# Diagnostics.net
KiCad netlist of a schematic drawn in Altium Designer
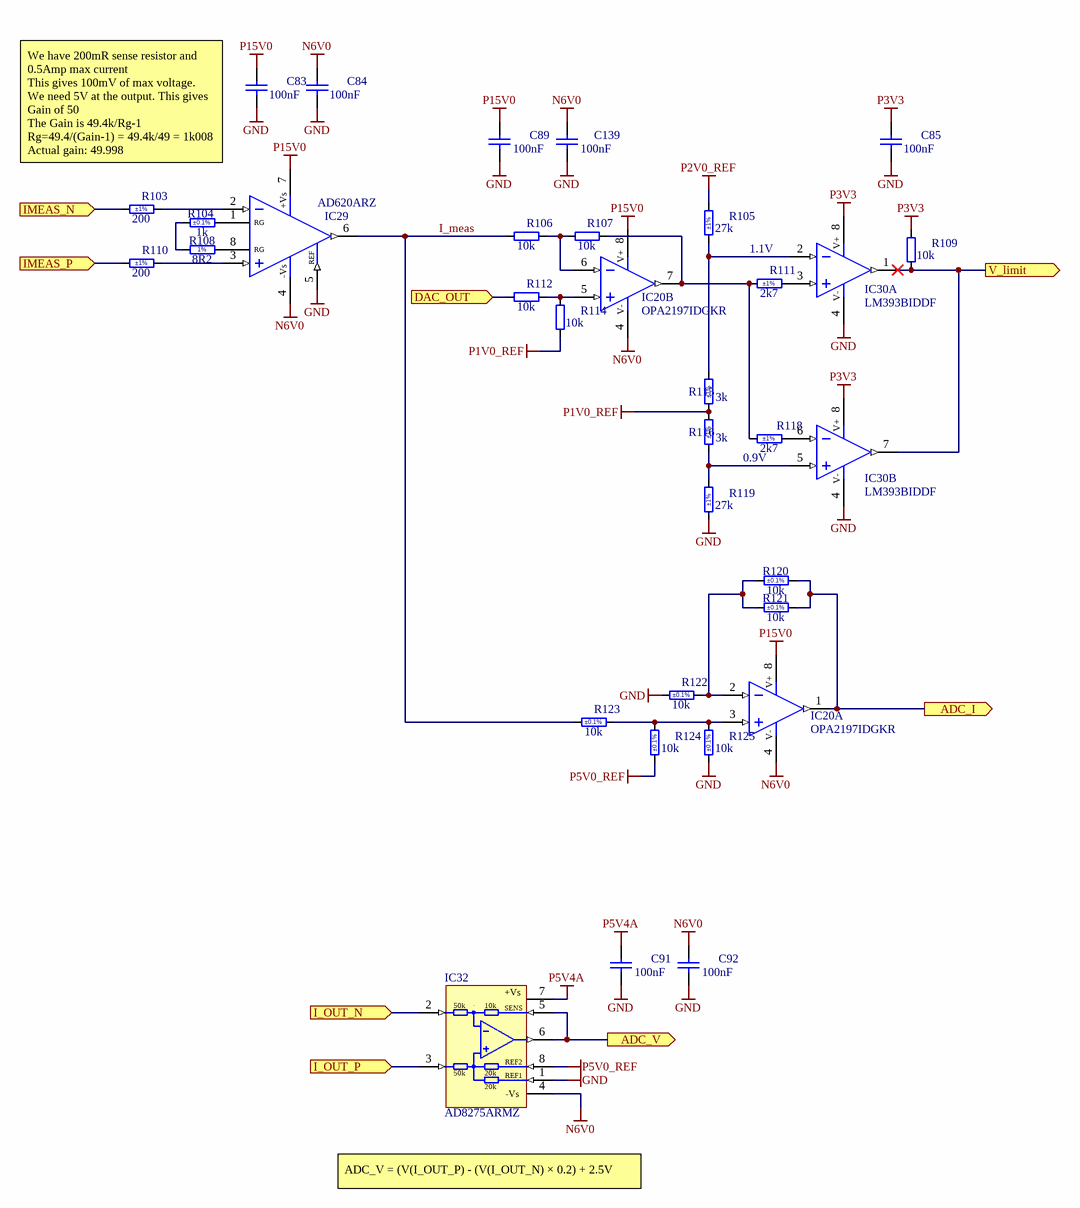
[diagram p0: Diagnostics.SchDoc]

(export (version "E")
  (design (tool "Eeschema 10.0.6"))
  (components
    (comp (ref "C83")
      (value "100nF")
      (footprint "CAPC1005X55N")
      (description "Non-polarised capacitor")
      (fields
        (field (name "PART NUMBER") "CC0402_100NF_16V_10%_X5R")
        (field (name "VOLTAGE") "16V")
        (field (name "AUTHOR") "CERN DEM JLC")
      )
      (libsource (lib "Capacitors") (part "Capacitor - non polarized"))
    )
    (comp (ref "C84")
      (value "100nF")
      (footprint "CAPC1005X55N")
      (description "Non-polarised capacitor")
      (fields
        (field (name "PART NUMBER") "CC0402_100NF_16V_10%_X5R")
        (field (name "VOLTAGE") "16V")
        (field (name "AUTHOR") "CERN DEM JLC")
      )
      (libsource (lib "Capacitors") (part "Capacitor - non polarized"))
    )
    (comp (ref "C85")
      (value "100nF")
      (footprint "CAPC1005X55N")
      (description "Non-polarised capacitor")
      (fields
        (field (name "PART NUMBER") "CC0402_100NF_16V_10%_X5R")
        (field (name "VOLTAGE") "16V")
        (field (name "AUTHOR") "CERN DEM JLC")
      )
      (libsource (lib "Capacitors") (part "Capacitor - non polarized"))
    )
    (comp (ref "C89")
      (value "100nF")
      (footprint "CAPC1005X55N")
      (description "Non-polarised capacitor")
      (fields
        (field (name "PART NUMBER") "CC0402_100NF_16V_10%_X5R")
        (field (name "VOLTAGE") "16V")
        (field (name "AUTHOR") "CERN DEM JLC")
      )
      (libsource (lib "Capacitors") (part "Capacitor - non polarized"))
    )
    (comp (ref "C91")
      (value "100nF")
      (footprint "CAPC1005X55N")
      (description "Non-polarised capacitor")
      (fields
        (field (name "PART NUMBER") "CC0402_100NF_16V_10%_X5R")
        (field (name "VOLTAGE") "16V")
        (field (name "AUTHOR") "CERN DEM JLC")
      )
      (libsource (lib "Capacitors") (part "Capacitor - non polarized"))
    )
    (comp (ref "C92")
      (value "100nF")
      (footprint "CAPC1005X55N")
      (description "Non-polarised capacitor")
      (fields
        (field (name "PART NUMBER") "CC0402_100NF_16V_10%_X5R")
        (field (name "VOLTAGE") "16V")
        (field (name "AUTHOR") "CERN DEM JLC")
      )
      (libsource (lib "Capacitors") (part "Capacitor - non polarized"))
    )
    (comp (ref "C139")
      (value "100nF")
      (footprint "CAPC1005X55N")
      (description "Non-polarised capacitor")
      (fields
        (field (name "PART NUMBER") "CC0402_100NF_16V_10%_X5R")
        (field (name "VOLTAGE") "16V")
        (field (name "AUTHOR") "CERN DEM JLC")
      )
      (libsource (lib "Capacitors") (part "Capacitor - non polarized"))
    )
    (comp (ref "IC20")
      (value "OPA2197IDGKR")
      (footprint "SOP65P490X110-8N")
      (description "36-V, Precision, Rail-to-Rail Input Output, Low Offset Voltage Op Amp 8-VSSOP")
      (fields (field (name "AUTHOR") "GK"))
      (libsource (lib "ICs_Analog_Interfaces") (part "OA_OPA2197IDGKR"))
    )
    (comp (ref "IC29")
      (value "AD620ARZ")
      (footprint "SOIC127P600X175-8N")
      (description "Low Cost Low Power Instrumentation Amplifier")
      (fields
        (field (name "MANUFACTURER1 PART NUMBER") "AD620ARZ-REEL7")
        (field (name "AUTHOR") "CERN DEM JLC")
      )
      (libsource (lib "ICs And Semiconductors") (part "AD620"))
    )
    (comp (ref "IC30")
      (value "LM393BIDDF")
      (footprint "SOT65P280X110-8N")
      (description "Dual Operational Amplifier")
      (fields (field (name "MANUFACTURER") "TEXAS INSTRUMENTS") (field (name "AUTHOR") "CERN DEM HF"))
      (libsource (lib "ICs And Semiconductors") (part "Operational Amplifier x2 Type1"))
    )
    (comp (ref "IC32")
      (value "AD8275ARMZ")
      (footprint "SOP65P490X110-8N")
      (description "G = 0.2, Level Translation, 16-Bit ADC Driver")
      (fields
        (field (name "MANUFACTURER") "ANALOG DEVICES")
        (field (name "MANUFACTURER PART NUMBER") "AD8275ARM")
        (field (name "AUTHOR") "CERN DEM JLC")
      )
      (libsource (lib "ICs And Semiconductors") (part "AD8275"))
    )
    (comp (ref "R103")
      (value "200")
      (footprint "RESC1608X55N")
      (description "Resistor - 1%")
      (fields
        (field (name "TOLERANCE") "±1%")
        (field (name "PART NUMBER") "R0603_200R_1%_0.1W_100PPM")
        (field (name "POWER") "0.1W")
        (field (name "AUTHOR") "CERN DEM JLC")
      )
      (libsource (lib "Resistors") (part "Resistor - 1%"))
    )
    (comp (ref "R104")
      (value "1k")
      (footprint "RESC1005X40N")
      (description "Resistor - 0.1%")
      (fields
        (field (name "TOLERANCE") "±0.1%")
        (field (name "PART NUMBER") "R0402_1K_0.1%_0.063W_25PPM")
        (field (name "POWER") "0.063W")
        (field (name "AUTHOR") "CERN DEM BC")
      )
      (libsource (lib "Resistors") (part "Resistor - 0.1%"))
    )
    (comp (ref "R105")
      (value "27k")
      (footprint "RESC1005X40N")
      (description "Resistor - 1%")
      (fields
        (field (name "TOLERANCE") "±1%")
        (field (name "PART NUMBER") "R0402_27K_1%_0.0625W_100PPM")
        (field (name "POWER") "0.0625W")
        (field (name "AUTHOR") "CERN DEM JLC")
      )
      (libsource (lib "Resistors") (part "Resistor - 1%"))
    )
    (comp (ref "R106")
      (value "10k")
      (footprint "RESC1005X35N")
      (description "Resistor - 0.1%")
      (fields
        (field (name "PART NUMBER") "R0402_10K_0.1%_0.063W_25PPM")
        (field (name "POWER") "0.063W")
        (field (name "AUTHOR") "CERN DEM JMW")
      )
      (libsource (lib "Resistors") (part "Resistor - 0.1%"))
    )
    (comp (ref "R107")
      (value "10k")
      (footprint "RESC1005X35N")
      (description "Resistor - 0.1%")
      (fields
        (field (name "PART NUMBER") "R0402_10K_0.1%_0.063W_25PPM")
        (field (name "POWER") "0.063W")
        (field (name "AUTHOR") "CERN DEM JMW")
      )
      (libsource (lib "Resistors") (part "Resistor - 0.1%"))
    )
    (comp (ref "R108")
      (value "8R2")
      (footprint "RESC1608X55N")
      (description "Resistor - 1%")
      (fields
        (field (name "PART NUMBER") "R0603_8R2_1%_0.1W_200PPM")
        (field (name "POWER") "0.1W")
        (field (name "AUTHOR") "CERN DEM JLC")
      )
      (libsource (lib "") (part "Resistor - 1%_1"))
    )
    (comp (ref "R109")
      (value "10k")
      (footprint "RESC1005X35N")
      (description "Resistor - 0.1%")
      (fields
        (field (name "PART NUMBER") "R0402_10K_0.1%_0.063W_25PPM")
        (field (name "POWER") "0.063W")
        (field (name "AUTHOR") "CERN DEM JMW")
      )
      (libsource (lib "Resistors") (part "Resistor - 0.1%"))
    )
    (comp (ref "R110")
      (value "200")
      (footprint "RESC1608X55N")
      (description "Resistor - 1%")
      (fields
        (field (name "TOLERANCE") "±1%")
        (field (name "PART NUMBER") "R0603_200R_1%_0.1W_100PPM")
        (field (name "POWER") "0.1W")
        (field (name "AUTHOR") "CERN DEM JLC")
      )
      (libsource (lib "Resistors") (part "Resistor - 1%"))
    )
    (comp (ref "R111")
      (value "2k7")
      (footprint "RESC1005X40N")
      (description "Resistor - 1%")
      (fields
        (field (name "TOLERANCE") "±1%")
        (field (name "PART NUMBER") "R0402_2K7_1%_0.0625W_100PPM")
        (field (name "POWER") "0.0625W")
        (field (name "AUTHOR") "CERN DEM HF")
      )
      (libsource (lib "Resistors") (part "Resistor - 1%"))
    )
    (comp (ref "R112")
      (value "10k")
      (footprint "RESC1005X35N")
      (description "Resistor - 0.1%")
      (fields
        (field (name "PART NUMBER") "R0402_10K_0.1%_0.063W_25PPM")
        (field (name "POWER") "0.063W")
        (field (name "AUTHOR") "CERN DEM JMW")
      )
      (libsource (lib "Resistors") (part "Resistor - 0.1%"))
    )
    (comp (ref "R114")
      (value "10k")
      (footprint "RESC1005X35N")
      (description "Resistor - 0.1%")
      (fields
        (field (name "PART NUMBER") "R0402_10K_0.1%_0.063W_25PPM")
        (field (name "POWER") "0.063W")
        (field (name "AUTHOR") "CERN DEM JMW")
      )
      (libsource (lib "Resistors") (part "Resistor - 0.1%"))
    )
    (comp (ref "R115")
      (value "3k")
      (footprint "RESC1005X40N")
      (description "Resistor - 1%")
      (fields
        (field (name "TOLERANCE") "±1%")
        (field (name "PART NUMBER") "R0402_3K_1%_0.0625W_100PPM")
        (field (name "POWER") "0.0625W")
        (field (name "AUTHOR") "CERN DEM JLC")
      )
      (libsource (lib "Resistors") (part "Resistor - 1%"))
    )
    (comp (ref "R116")
      (value "3k")
      (footprint "RESC1005X40N")
      (description "Resistor - 1%")
      (fields
        (field (name "TOLERANCE") "±1%")
        (field (name "PART NUMBER") "R0402_3K_1%_0.0625W_100PPM")
        (field (name "POWER") "0.0625W")
        (field (name "AUTHOR") "CERN DEM JLC")
      )
      (libsource (lib "Resistors") (part "Resistor - 1%"))
    )
    (comp (ref "R118")
      (value "2k7")
      (footprint "RESC1005X40N")
      (description "Resistor - 1%")
      (fields
        (field (name "TOLERANCE") "±1%")
        (field (name "PART NUMBER") "R0402_2K7_1%_0.0625W_100PPM")
        (field (name "POWER") "0.0625W")
        (field (name "AUTHOR") "CERN DEM HF")
      )
      (libsource (lib "Resistors") (part "Resistor - 1%"))
    )
    (comp (ref "R119")
      (value "27k")
      (footprint "RESC1005X40N")
      (description "Resistor - 1%")
      (fields
        (field (name "TOLERANCE") "±1%")
        (field (name "PART NUMBER") "R0402_27K_1%_0.0625W_100PPM")
        (field (name "POWER") "0.0625W")
        (field (name "AUTHOR") "CERN DEM JLC")
      )
      (libsource (lib "Resistors") (part "Resistor - 1%"))
    )
    (comp (ref "R120")
      (value "10k")
      (footprint "RESC1005X35N")
      (description "Resistor - 0.1%")
      (fields
        (field (name "TOLERANCE") "±0.1%")
        (field (name "PART NUMBER") "R0402_10K_0.1%_0.063W_25PPM")
        (field (name "POWER") "0.063W")
        (field (name "AUTHOR") "CERN DEM JMW")
      )
      (libsource (lib "Resistors") (part "Resistor - 0.1%"))
    )
    (comp (ref "R121")
      (value "10k")
      (footprint "RESC1005X35N")
      (description "Resistor - 0.1%")
      (fields
        (field (name "TOLERANCE") "±0.1%")
        (field (name "PART NUMBER") "R0402_10K_0.1%_0.063W_25PPM")
        (field (name "POWER") "0.063W")
        (field (name "AUTHOR") "CERN DEM JMW")
      )
      (libsource (lib "Resistors") (part "Resistor - 0.1%"))
    )
    (comp (ref "R122")
      (value "10k")
      (footprint "RESC1005X35N")
      (description "Resistor - 0.1%")
      (fields
        (field (name "TOLERANCE") "±0.1%")
        (field (name "PART NUMBER") "R0402_10K_0.1%_0.063W_25PPM")
        (field (name "POWER") "0.063W")
        (field (name "AUTHOR") "CERN DEM JMW")
      )
      (libsource (lib "Resistors") (part "Resistor - 0.1%"))
    )
    (comp (ref "R123")
      (value "10k")
      (footprint "RESC1005X35N")
      (description "Resistor - 0.1%")
      (fields
        (field (name "TOLERANCE") "±0.1%")
        (field (name "PART NUMBER") "R0402_10K_0.1%_0.063W_25PPM")
        (field (name "POWER") "0.063W")
        (field (name "AUTHOR") "CERN DEM JMW")
      )
      (libsource (lib "Resistors") (part "Resistor - 0.1%"))
    )
    (comp (ref "R124")
      (value "10k")
      (footprint "RESC1005X35N")
      (description "Resistor - 0.1%")
      (fields
        (field (name "TOLERANCE") "±0.1%")
        (field (name "PART NUMBER") "R0402_10K_0.1%_0.063W_25PPM")
        (field (name "POWER") "0.063W")
        (field (name "AUTHOR") "CERN DEM JMW")
      )
      (libsource (lib "Resistors") (part "Resistor - 0.1%"))
    )
    (comp (ref "R125")
      (value "10k")
      (footprint "RESC1005X35N")
      (description "Resistor - 0.1%")
      (fields
        (field (name "TOLERANCE") "±0.1%")
        (field (name "PART NUMBER") "R0402_10K_0.1%_0.063W_25PPM")
        (field (name "POWER") "0.063W")
        (field (name "AUTHOR") "CERN DEM JMW")
      )
      (libsource (lib "Resistors") (part "Resistor - 0.1%"))
    )
  )
  (nets
    (net (code "1") (name "/ADC_I") (class "Default")
      (node (ref "IC20") (pin "1") (pinfunction "OUT_1") (pintype "output"))
      (node (ref "R120") (pin "2") (pinfunction "2_2") (pintype "passive"))
      (node (ref "R121") (pin "2") (pinfunction "2_2") (pintype "passive"))
    )
    (net (code "2") (name "/ADC_V") (class "Default")
      (node (ref "IC32") (pin "5") (pinfunction "SENSE_5") (pintype "input"))
      (node (ref "IC32") (pin "6") (pinfunction "OUT_6") (pintype "output"))
    )
    (net (code "3") (name "/DAC_OUT") (class "Default")
      (node (ref "R112") (pin "1") (pinfunction "1_1") (pintype "passive"))
    )
    (net (code "4") (name "/IMEAS_N") (class "Default")
      (node (ref "R103") (pin "1") (pinfunction "1_1") (pintype "passive"))
    )
    (net (code "5") (name "/IMEAS_P") (class "Default")
      (node (ref "R110") (pin "1") (pinfunction "1_1") (pintype "passive"))
    )
    (net (code "6") (name "/I_OUT_N") (class "Default")
      (node (ref "IC32") (pin "2") (pinfunction "IN-_2") (pintype "input"))
    )
    (net (code "7") (name "/I_OUT_P") (class "Default")
      (node (ref "IC32") (pin "3") (pinfunction "IN+_3") (pintype "input"))
    )
    (net (code "8") (name "/I_meas") (class "Default")
      (node (ref "IC29") (pin "6") (pinfunction "Vout_6") (pintype "output"))
      (node (ref "R106") (pin "1") (pinfunction "1_1") (pintype "passive"))
      (node (ref "R123") (pin "1") (pinfunction "1_1") (pintype "passive"))
    )
    (net (code "9") (name "/V_limit") (class "Default")
      (node (ref "IC30") (pin "1") (pinfunction "OUT_1") (pintype "output"))
      (node (ref "IC30") (pin "7") (pinfunction "OUT_7") (pintype "output"))
      (node (ref "R109") (pin "1") (pinfunction "1_1") (pintype "passive"))
    )
    (net (code "10") (name "GND") (class "Default")
      (node (ref "C139") (pin "1") (pinfunction "1_1") (pintype "passive"))
      (node (ref "C83") (pin "1") (pinfunction "1_1") (pintype "passive"))
      (node (ref "C84") (pin "1") (pinfunction "1_1") (pintype "passive"))
      (node (ref "C85") (pin "1") (pinfunction "1_1") (pintype "passive"))
      (node (ref "C89") (pin "1") (pinfunction "1_1") (pintype "passive"))
      (node (ref "C91") (pin "1") (pinfunction "1_1") (pintype "passive"))
      (node (ref "C92") (pin "1") (pinfunction "1_1") (pintype "passive"))
      (node (ref "IC29") (pin "5") (pinfunction "REF_5") (pintype "input"))
      (node (ref "IC30") (pin "4") (pinfunction "V-_4") (pintype "power_in"))
      (node (ref "IC32") (pin "1") (pinfunction "REF1_1") (pintype "input"))
      (node (ref "R119") (pin "1") (pinfunction "1_1") (pintype "passive"))
      (node (ref "R122") (pin "1") (pinfunction "1_1") (pintype "passive"))
      (node (ref "R125") (pin "1") (pinfunction "1_1") (pintype "passive"))
    )
    (net (code "11") (name "N6V0") (class "Default")
      (node (ref "C139") (pin "2") (pinfunction "2_2") (pintype "passive"))
      (node (ref "C84") (pin "2") (pinfunction "2_2") (pintype "passive"))
      (node (ref "C92") (pin "2") (pinfunction "2_2") (pintype "passive"))
      (node (ref "IC20") (pin "4") (pinfunction "V-_4") (pintype "power_in"))
      (node (ref "IC29") (pin "4") (pinfunction "-Vs_4") (pintype "power_in"))
      (node (ref "IC32") (pin "4") (pinfunction "-Vs_4") (pintype "power_in"))
    )
    (net (code "12") (name "Net-(IC20A-IN+)") (class "Default")
      (node (ref "IC20") (pin "3") (pinfunction "IN+_3") (pintype "input"))
      (node (ref "R123") (pin "2") (pinfunction "2_2") (pintype "passive"))
      (node (ref "R124") (pin "2") (pinfunction "2_2") (pintype "passive"))
      (node (ref "R125") (pin "2") (pinfunction "2_2") (pintype "passive"))
    )
    (net (code "13") (name "Net-(IC20A-IN-)") (class "Default")
      (node (ref "IC20") (pin "2") (pinfunction "IN-_2") (pintype "input"))
      (node (ref "R120") (pin "1") (pinfunction "1_1") (pintype "passive"))
      (node (ref "R121") (pin "1") (pinfunction "1_1") (pintype "passive"))
      (node (ref "R122") (pin "2") (pinfunction "2_2") (pintype "passive"))
    )
    (net (code "14") (name "Net-(IC20B-IN+)") (class "Default")
      (node (ref "IC20") (pin "5") (pinfunction "IN+_5") (pintype "input"))
      (node (ref "R112") (pin "2") (pinfunction "2_2") (pintype "passive"))
      (node (ref "R114") (pin "2") (pinfunction "2_2") (pintype "passive"))
    )
    (net (code "15") (name "Net-(IC20B-IN-)") (class "Default")
      (node (ref "IC20") (pin "6") (pinfunction "IN-_6") (pintype "input"))
      (node (ref "R106") (pin "2") (pinfunction "2_2") (pintype "passive"))
      (node (ref "R107") (pin "1") (pinfunction "1_1") (pintype "passive"))
    )
    (net (code "16") (name "Net-(IC20B-OUT)") (class "Default")
      (node (ref "IC20") (pin "7") (pinfunction "OUT_7") (pintype "output"))
      (node (ref "R107") (pin "2") (pinfunction "2_2") (pintype "passive"))
      (node (ref "R111") (pin "1") (pinfunction "1_1") (pintype "passive"))
      (node (ref "R118") (pin "1") (pinfunction "1_1") (pintype "passive"))
    )
    (net (code "17") (name "Net-(IC29-+IN)") (class "Default")
      (node (ref "IC29") (pin "3") (pinfunction "+IN_3") (pintype "input"))
      (node (ref "R110") (pin "2") (pinfunction "2_2") (pintype "passive"))
    )
    (net (code "18") (name "Net-(IC29-+RG)") (class "Default")
      (node (ref "IC29") (pin "8") (pinfunction "+RG_8") (pintype "passive"))
      (node (ref "R108") (pin "2") (pinfunction "2_2") (pintype "passive"))
    )
    (net (code "19") (name "Net-(IC29--IN)") (class "Default")
      (node (ref "IC29") (pin "2") (pinfunction "-IN_2") (pintype "input"))
      (node (ref "R103") (pin "2") (pinfunction "2_2") (pintype "passive"))
    )
    (net (code "20") (name "Net-(IC29--RG)") (class "Default")
      (node (ref "IC29") (pin "1") (pinfunction "-RG_1") (pintype "passive"))
      (node (ref "R104") (pin "2") (pinfunction "2_2") (pintype "passive"))
    )
    (net (code "21") (name "Net-(IC30A-IN+)") (class "Default")
      (node (ref "IC30") (pin "3") (pinfunction "IN+_3") (pintype "input"))
      (node (ref "R111") (pin "2") (pinfunction "2_2") (pintype "passive"))
    )
    (net (code "22") (name "Net-(IC30A-IN-)") (class "Default")
      (node (ref "IC30") (pin "2") (pinfunction "IN-_2") (pintype "input"))
      (node (ref "R105") (pin "1") (pinfunction "1_1") (pintype "passive"))
      (node (ref "R115") (pin "2") (pinfunction "2_2") (pintype "passive"))
    )
    (net (code "23") (name "Net-(IC30B-IN+)") (class "Default")
      (node (ref "IC30") (pin "5") (pinfunction "IN+_5") (pintype "input"))
      (node (ref "R116") (pin "1") (pinfunction "1_1") (pintype "passive"))
      (node (ref "R119") (pin "2") (pinfunction "2_2") (pintype "passive"))
    )
    (net (code "24") (name "Net-(IC30B-IN-)") (class "Default")
      (node (ref "IC30") (pin "6") (pinfunction "IN-_6") (pintype "input"))
      (node (ref "R118") (pin "2") (pinfunction "2_2") (pintype "passive"))
    )
    (net (code "25") (name "Net-(R104-Pad1)") (class "Default")
      (node (ref "R104") (pin "1") (pinfunction "1_1") (pintype "passive"))
      (node (ref "R108") (pin "1") (pinfunction "1_1") (pintype "passive"))
    )
    (net (code "26") (name "P1V0_REF") (class "Default")
      (node (ref "R114") (pin "1") (pinfunction "1_1") (pintype "passive"))
      (node (ref "R115") (pin "1") (pinfunction "1_1") (pintype "passive"))
      (node (ref "R116") (pin "2") (pinfunction "2_2") (pintype "passive"))
    )
    (net (code "27") (name "P2V0_REF") (class "Default")
      (node (ref "R105") (pin "2") (pinfunction "2_2") (pintype "passive"))
    )
    (net (code "28") (name "P3V3") (class "Default")
      (node (ref "C85") (pin "2") (pinfunction "2_2") (pintype "passive"))
      (node (ref "IC30") (pin "8") (pinfunction "V+_8") (pintype "power_in"))
      (node (ref "R109") (pin "2") (pinfunction "2_2") (pintype "passive"))
    )
    (net (code "29") (name "P5V0_REF") (class "Default")
      (node (ref "IC32") (pin "8") (pinfunction "REF2_8") (pintype "input"))
      (node (ref "R124") (pin "1") (pinfunction "1_1") (pintype "passive"))
    )
    (net (code "30") (name "P5V4A") (class "Default")
      (node (ref "C91") (pin "2") (pinfunction "2_2") (pintype "passive"))
      (node (ref "IC32") (pin "7") (pinfunction "+Vs_7") (pintype "power_in"))
    )
    (net (code "31") (name "P15V0") (class "Default")
      (node (ref "C83") (pin "2") (pinfunction "2_2") (pintype "passive"))
      (node (ref "C89") (pin "2") (pinfunction "2_2") (pintype "passive"))
      (node (ref "IC20") (pin "8") (pinfunction "V+_8") (pintype "power_in"))
      (node (ref "IC29") (pin "7") (pinfunction "+Vs_7") (pintype "power_in"))
    )
  )
)
